# AND_gate.net
KiCad netlist of a schematic drawn in EAGLE
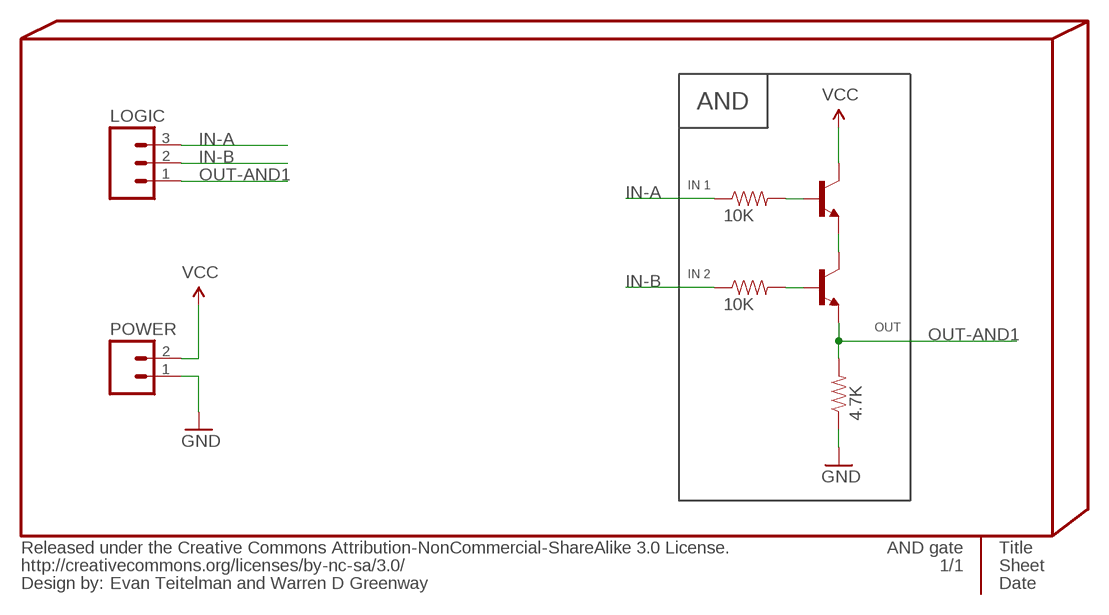
[diagram p0: schematic, sheet 1]

(export (version "E")
  (design (tool "Eeschema 10.0.6"))
  (components
    (comp (ref "INFO4")
      (value "Evan Teitelman and Warren D Greenway")
      (footprint "eagle-import:%CC-NC-SA")
      (libsource (lib "eagle-import") (part "%CC-NC-SA"))
    )
    (comp (ref "LOGIC")
      (value "M03PTH")
      (footprint "eagle-import:1X03")
      (libsource (lib "eagle-import") (part "M03PTH"))
    )
    (comp (ref "PDR-AND1")
      (value "4.7K")
      (footprint "eagle-import:0402-RES")
      (libsource (lib "eagle-import") (part "RESISTOR0402-RES"))
    )
    (comp (ref "POWER")
      (value "M02PTH")
      (footprint "eagle-import:1X02")
      (libsource (lib "eagle-import") (part "M02PTH"))
    )
    (comp (ref "Q1-AND1")
      (value "TRANSISTOR_NPNSOT23")
      (footprint "eagle-import:SOT23")
      (libsource (lib "eagle-import") (part "TRANSISTOR_NPNSOT23"))
    )
    (comp (ref "Q2-AND1")
      (value "TRANSISTOR_NPNSOT23")
      (footprint "eagle-import:SOT23")
      (libsource (lib "eagle-import") (part "TRANSISTOR_NPNSOT23"))
    )
    (comp (ref "R1-AND1")
      (value "10K")
      (footprint "eagle-import:0402-RES")
      (libsource (lib "eagle-import") (part "RESISTOR0402-RES"))
    )
    (comp (ref "R2-AND1")
      (value "10K")
      (footprint "eagle-import:0402-RES")
      (libsource (lib "eagle-import") (part "RESISTOR0402-RES"))
    )
  )
  (nets
    (net (code "1") (name "/IN-A") (class "Default")
      (node (ref "LOGIC") (pin "3") (pinfunction "3_3") (pintype "passive"))
      (node (ref "R1-AND1") (pin "1") (pinfunction "1_1") (pintype "passive"))
    )
    (net (code "2") (name "/IN-B") (class "Default")
      (node (ref "LOGIC") (pin "2") (pinfunction "2_2") (pintype "passive"))
      (node (ref "R2-AND1") (pin "1") (pinfunction "1_1") (pintype "passive"))
    )
    (net (code "3") (name "/OUT-AND1") (class "Default")
      (node (ref "LOGIC") (pin "1") (pinfunction "1_1") (pintype "passive"))
      (node (ref "PDR-AND1") (pin "2") (pinfunction "2_2") (pintype "passive"))
      (node (ref "Q2-AND1") (pin "2") (pinfunction "E_2") (pintype "passive"))
    )
    (net (code "4") (name "@GND") (class "Default")
      (node (ref "PDR-AND1") (pin "1") (pinfunction "1_1") (pintype "passive"))
      (node (ref "POWER") (pin "1") (pinfunction "1_1") (pintype "passive"))
    )
    (net (code "5") (name "@VCC") (class "Default")
      (node (ref "POWER") (pin "2") (pinfunction "2_2") (pintype "passive"))
      (node (ref "Q1-AND1") (pin "3") (pinfunction "C_3") (pintype "passive"))
    )
    (net (code "6") (name "Net-(Q1-AND1-B)") (class "Default")
      (node (ref "Q1-AND1") (pin "1") (pinfunction "B_1") (pintype "passive"))
      (node (ref "R1-AND1") (pin "2") (pinfunction "2_2") (pintype "passive"))
    )
    (net (code "7") (name "Net-(Q1-AND1-E)") (class "Default")
      (node (ref "Q1-AND1") (pin "2") (pinfunction "E_2") (pintype "passive"))
      (node (ref "Q2-AND1") (pin "3") (pinfunction "C_3") (pintype "passive"))
    )
    (net (code "8") (name "Net-(Q2-AND1-B)") (class "Default")
      (node (ref "Q2-AND1") (pin "1") (pinfunction "B_1") (pintype "passive"))
      (node (ref "R2-AND1") (pin "2") (pinfunction "2_2") (pintype "passive"))
    )
  )
)
